# CAN_SPI.net
KiCad netlist of a schematic drawn in EAGLE
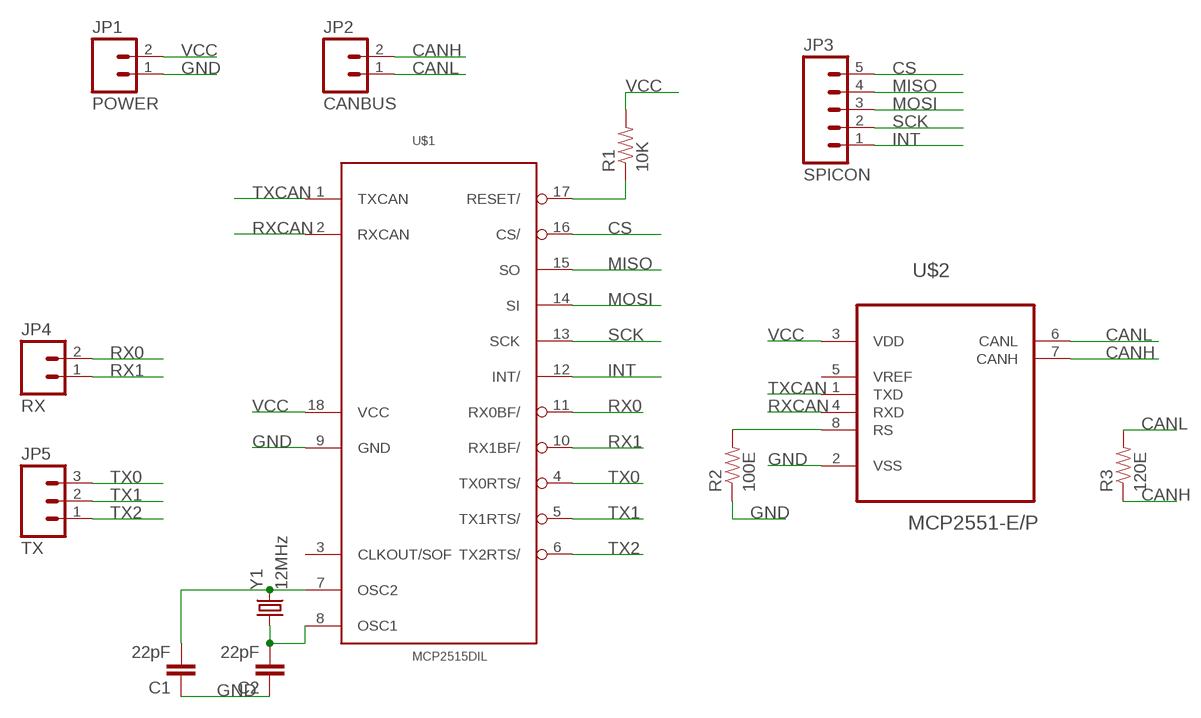
[diagram p0: schematic, sheet 1]

(export (version "E")
  (design (tool "Eeschema 10.0.6"))
  (components
    (comp (ref "C1")
      (value "22pF")
      (footprint "eagle-import:CAP-PTH-SMALL-KIT")
      (libsource (lib "eagle-import") (part "0.1UF-50V-20%(PTH)KIT-EZ"))
    )
    (comp (ref "C2")
      (value "22pF")
      (footprint "eagle-import:CAP-PTH-SMALL-KIT")
      (libsource (lib "eagle-import") (part "0.1UF-50V-20%(PTH)KIT-EZ"))
    )
    (comp (ref "JP1")
      (value "POWER")
      (footprint "eagle-import:1X02_LONGPADS")
      (libsource (lib "eagle-import") (part "M02PTH3"))
    )
    (comp (ref "JP2")
      (value "CANBUS")
      (footprint "eagle-import:1X02_LONGPADS")
      (libsource (lib "eagle-import") (part "M02PTH3"))
    )
    (comp (ref "JP3")
      (value "SPICON")
      (footprint "eagle-import:1X05_LONGPADS")
      (libsource (lib "eagle-import") (part "M05PTH_LONGPADS"))
    )
    (comp (ref "JP4")
      (value "RX")
      (footprint "eagle-import:1X02_LONGPADS")
      (libsource (lib "eagle-import") (part "M02PTH3"))
    )
    (comp (ref "JP5")
      (value "TX")
      (footprint "eagle-import:1X03_LONGPADS")
      (libsource (lib "eagle-import") (part "M03LONGPADS"))
    )
    (comp (ref "R1")
      (value "10K")
      (footprint "eagle-import:AXIAL-0.3")
      (libsource (lib "eagle-import") (part "1KOHM-1/4W-1%(PTH)"))
    )
    (comp (ref "R2")
      (value "100E")
      (footprint "eagle-import:AXIAL-0.3")
      (libsource (lib "eagle-import") (part "1KOHM-1/4W-1%(PTH)"))
    )
    (comp (ref "R3")
      (value "120E")
      (footprint "eagle-import:AXIAL-0.3")
      (libsource (lib "eagle-import") (part "1KOHM-1/4W-1%(PTH)"))
    )
    (comp (ref "U$1")
      (value "MCP2515DIL")
      (footprint "eagle-import:DIL18")
      (libsource (lib "eagle-import") (part "MCP2515DIL"))
    )
    (comp (ref "U$2")
      (value "MCP2551-E/P")
      (footprint "eagle-import:DIP254P762X432-8")
      (libsource (lib "eagle-import") (part "MCP2551-E/P"))
    )
    (comp (ref "Y1")
      (value "12MHz")
      (footprint "eagle-import:HC49US")
      (libsource (lib "eagle-import") (part "CRYSTALHC49US"))
    )
  )
  (nets
    (net (code "1") (name "/CANH") (class "Default")
      (node (ref "JP2") (pin "2") (pinfunction "2_2") (pintype "passive"))
      (node (ref "R3") (pin "P$1") (pinfunction "1_P$1") (pintype "passive"))
      (node (ref "U$2") (pin "7") (pinfunction "CANH_7") (pintype "output"))
    )
    (net (code "2") (name "/CANL") (class "Default")
      (node (ref "JP2") (pin "1") (pinfunction "1_1") (pintype "passive"))
      (node (ref "R3") (pin "P$2") (pinfunction "2_P$2") (pintype "passive"))
      (node (ref "U$2") (pin "6") (pinfunction "CANL_6") (pintype "output"))
    )
    (net (code "3") (name "/CS") (class "Default")
      (node (ref "JP3") (pin "5") (pinfunction "5_5") (pintype "passive"))
      (node (ref "U$1") (pin "16") (pinfunction "CS/_16") (pintype "input"))
    )
    (net (code "4") (name "/GND") (class "Default")
      (node (ref "C1") (pin "1") (pinfunction "1_1") (pintype "passive"))
      (node (ref "C2") (pin "1") (pinfunction "1_1") (pintype "passive"))
      (node (ref "JP1") (pin "1") (pinfunction "1_1") (pintype "passive"))
      (node (ref "R2") (pin "P$1") (pinfunction "1_P$1") (pintype "passive"))
      (node (ref "U$1") (pin "9") (pinfunction "GND_9") (pintype "power_in"))
      (node (ref "U$2") (pin "2") (pinfunction "VSS_2") (pintype "passive"))
    )
    (net (code "5") (name "/INT") (class "Default")
      (node (ref "JP3") (pin "1") (pinfunction "1_1") (pintype "passive"))
      (node (ref "U$1") (pin "12") (pinfunction "INT/_12") (pintype "output"))
    )
    (net (code "6") (name "/MISO") (class "Default")
      (node (ref "JP3") (pin "4") (pinfunction "4_4") (pintype "passive"))
      (node (ref "U$1") (pin "15") (pinfunction "SO_15") (pintype "output"))
    )
    (net (code "7") (name "/MOSI") (class "Default")
      (node (ref "JP3") (pin "3") (pinfunction "3_3") (pintype "passive"))
      (node (ref "U$1") (pin "14") (pinfunction "SI_14") (pintype "input"))
    )
    (net (code "8") (name "/RX0") (class "Default")
      (node (ref "JP4") (pin "2") (pinfunction "2_2") (pintype "passive"))
      (node (ref "U$1") (pin "11") (pinfunction "RX0BF/_11") (pintype "bidirectional"))
    )
    (net (code "9") (name "/RX1") (class "Default")
      (node (ref "JP4") (pin "1") (pinfunction "1_1") (pintype "passive"))
      (node (ref "U$1") (pin "10") (pinfunction "RX1BF/_10") (pintype "bidirectional"))
    )
    (net (code "10") (name "/RXCAN") (class "Default")
      (node (ref "U$1") (pin "2") (pinfunction "RXCAN_2") (pintype "input"))
      (node (ref "U$2") (pin "4") (pinfunction "RXD_4") (pintype "input"))
    )
    (net (code "11") (name "/SCK") (class "Default")
      (node (ref "JP3") (pin "2") (pinfunction "2_2") (pintype "passive"))
      (node (ref "U$1") (pin "13") (pinfunction "SCK_13") (pintype "input"))
    )
    (net (code "12") (name "/TX0") (class "Default")
      (node (ref "JP5") (pin "3") (pinfunction "3_3") (pintype "passive"))
      (node (ref "U$1") (pin "4") (pinfunction "TX0RTS/_4") (pintype "bidirectional"))
    )
    (net (code "13") (name "/TX1") (class "Default")
      (node (ref "JP5") (pin "2") (pinfunction "2_2") (pintype "passive"))
      (node (ref "U$1") (pin "5") (pinfunction "TX1RTS/_5") (pintype "bidirectional"))
    )
    (net (code "14") (name "/TX2") (class "Default")
      (node (ref "JP5") (pin "1") (pinfunction "1_1") (pintype "passive"))
      (node (ref "U$1") (pin "6") (pinfunction "TX2RTS/_6") (pintype "bidirectional"))
    )
    (net (code "15") (name "/TXCAN") (class "Default")
      (node (ref "U$1") (pin "1") (pinfunction "TXCAN_1") (pintype "output"))
      (node (ref "U$2") (pin "1") (pinfunction "TXD_1") (pintype "input"))
    )
    (net (code "16") (name "/VCC") (class "Default")
      (node (ref "JP1") (pin "2") (pinfunction "2_2") (pintype "passive"))
      (node (ref "R1") (pin "P$2") (pinfunction "2_P$2") (pintype "passive"))
      (node (ref "U$1") (pin "18") (pinfunction "VCC_18") (pintype "power_in"))
      (node (ref "U$2") (pin "3") (pinfunction "VDD_3") (pintype "power_in"))
    )
    (net (code "17") (name "Net-(R1-1)") (class "Default")
      (node (ref "R1") (pin "P$1") (pinfunction "1_P$1") (pintype "passive"))
      (node (ref "U$1") (pin "17") (pinfunction "RESET/_17") (pintype "input"))
    )
    (net (code "18") (name "Net-(R2-2)") (class "Default")
      (node (ref "R2") (pin "P$2") (pinfunction "2_P$2") (pintype "passive"))
      (node (ref "U$2") (pin "8") (pinfunction "RS_8") (pintype "input"))
    )
    (net (code "19") (name "Net-(U$1-OSC1)") (class "Default")
      (node (ref "C2") (pin "2") (pinfunction "2_2") (pintype "passive"))
      (node (ref "U$1") (pin "8") (pinfunction "OSC1_8") (pintype "bidirectional"))
      (node (ref "Y1") (pin "1") (pinfunction "1_1") (pintype "passive"))
    )
    (net (code "20") (name "Net-(U$1-OSC2)") (class "Default")
      (node (ref "C1") (pin "2") (pinfunction "2_2") (pintype "passive"))
      (node (ref "U$1") (pin "7") (pinfunction "OSC2_7") (pintype "bidirectional"))
      (node (ref "Y1") (pin "2") (pinfunction "2_2") (pintype "passive"))
    )
    (net (code "21") (name "unconnected-(U$1-CLKOUT{slash}SOF-Pad3)") (class "Default")
      (node (ref "U$1") (pin "3") (pinfunction "CLKOUT/SOF_3") (pintype "bidirectional"))
    )
    (net (code "22") (name "unconnected-(U$2-VREF-Pad5)") (class "Default")
      (node (ref "U$2") (pin "5") (pinfunction "VREF_5") (pintype "input"))
    )
  )
)
